# Power_Management_RFMC_RTM.net
KiCad netlist of a schematic drawn in Altium Designer
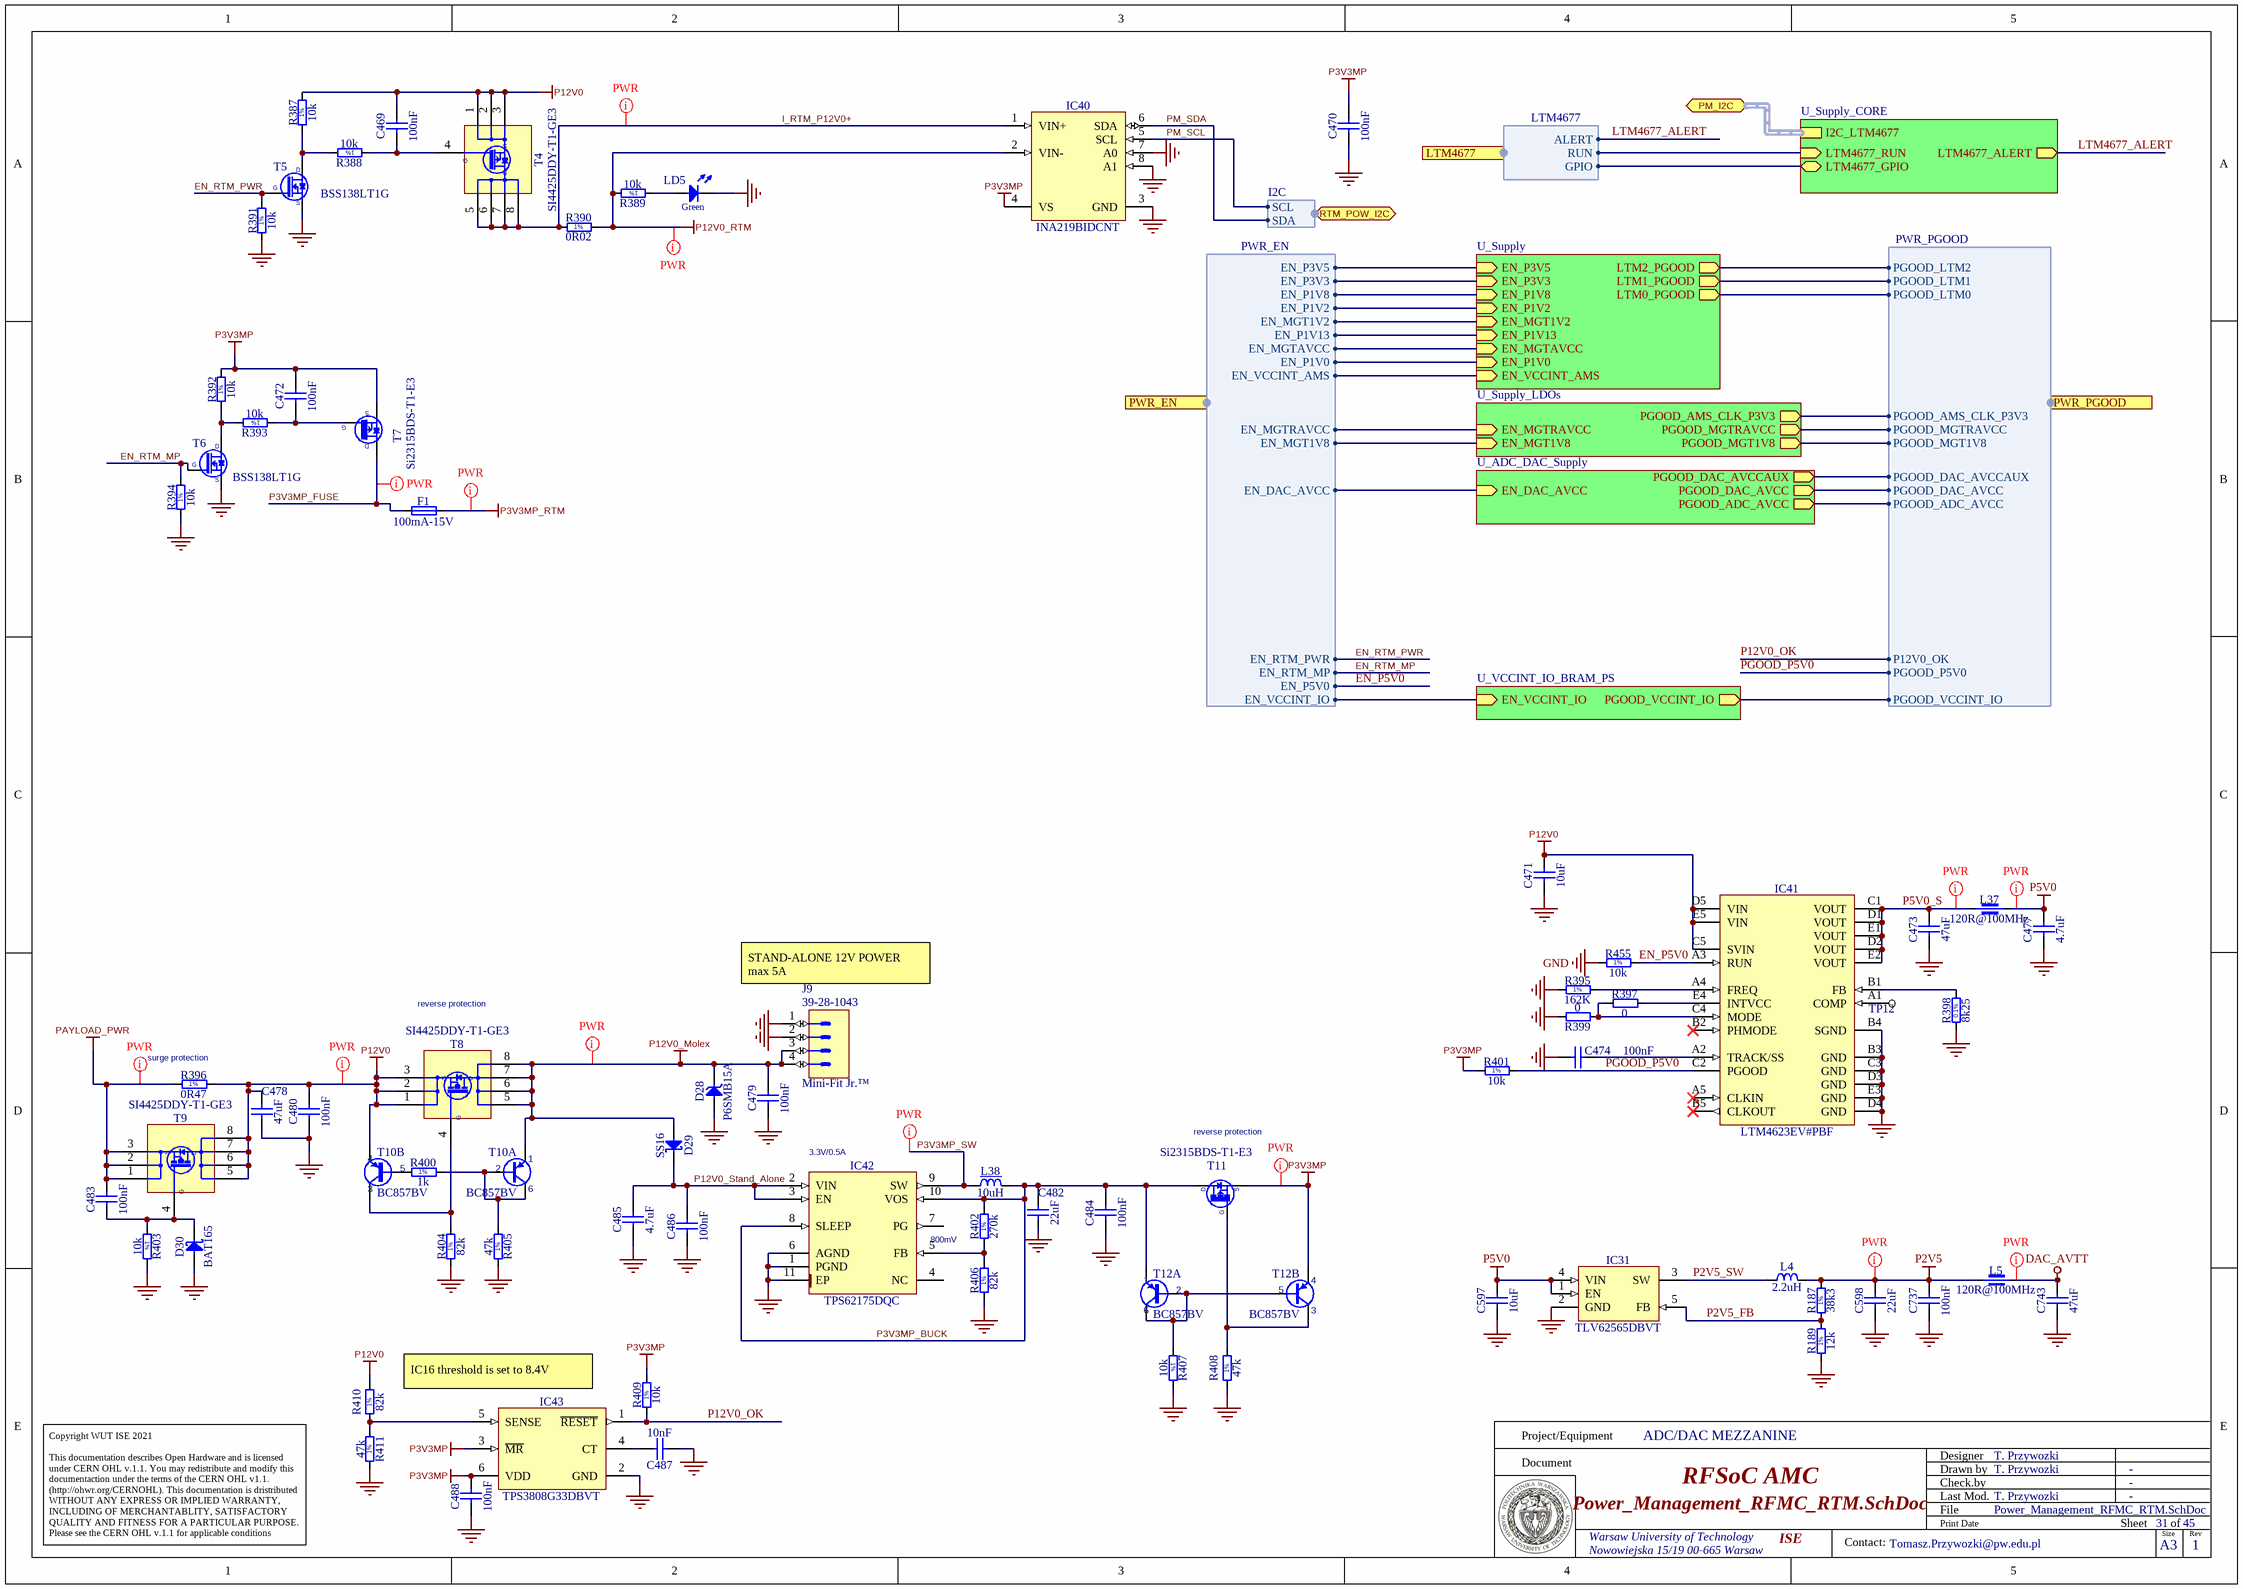
[diagram p0: Power_Management_RFMC_RTM.SchDoc]

(export (version "E")
  (design (tool "Eeschema 10.0.6"))
  (components
    (comp (ref "C469")
      (value "100nF")
      (footprint "CAPC1005X55N")
      (description "Non-polarised capacitor")
      (fields
        (field (name "MANUFACTURER PART NUMBER") "CC0402_100NF_16V_10%_X5R")
        (field (name "MANUFACTURER") "GENERIC")
        (field (name "AUTHOR") "CERN DEM JLC")
      )
      (libsource (lib "Capacitors") (part "Capacitor - non polarized"))
    )
    (comp (ref "C470")
      (value "100nF")
      (footprint "CAPC1005X55N")
      (description "Non-polarised capacitor")
      (fields
        (field (name "MANUFACTURER PART NUMBER") "CC0402_100NF_16V_10%_X5R")
        (field (name "MANUFACTURER") "GENERIC")
        (field (name "AUTHOR") "CERN DEM JLC")
      )
      (libsource (lib "Capacitors") (part "Capacitor - non polarized"))
    )
    (comp (ref "C471")
      (value "10uF")
      (footprint "CAPC2012X95N")
      (description "Non-polarised capacitor")
      (fields
        (field (name "PART NUMBER") "CC0805_10UF_25V_10%_X5R")
        (field (name "VOLTAGE") "25V")
        (field (name "AUTHOR") "CERN DEM JLC")
      )
      (libsource (lib "Capacitors") (part "Capacitor - non polarized"))
    )
    (comp (ref "C472")
      (value "100nF")
      (footprint "CAPC1005X55N")
      (description "Non-polarised capacitor")
      (fields
        (field (name "MANUFACTURER PART NUMBER") "CC0402_100NF_16V_10%_X5R")
        (field (name "MANUFACTURER") "GENERIC")
        (field (name "AUTHOR") "CERN DEM JLC")
      )
      (libsource (lib "Capacitors") (part "Capacitor - non polarized"))
    )
    (comp (ref "C473")
      (value "47uF")
      (footprint "CAPC2012X140N")
      (description "Non-polarised capacitor")
      (fields
        (field (name "MANUFACTURER PART NUMBER") "CC0805_47UF_6.3V_20%_X5R")
        (field (name "MANUFACTURER") "GENERIC")
        (field (name "AUTHOR") "CERN DEM JLC")
      )
      (libsource (lib "Capacitors") (part "Capacitor - non polarized"))
    )
    (comp (ref "C474")
      (value "100nF")
      (footprint "CAPC1005X55N")
      (description "Non-polarised capacitor")
      (fields
        (field (name "PART NUMBER") "CC0402_100NF_16V_10%_X5R")
        (field (name "VOLTAGE") "16V")
        (field (name "AUTHOR") "CERN DEM JLC")
      )
      (libsource (lib "Capacitors") (part "Capacitor - non polarized"))
    )
    (comp (ref "C477")
      (value "4.7uF")
      (footprint "CAPC1709X95N")
      (description "Non-polarised capacitor")
      (fields
        (field (name "MANUFACTURER PART NUMBER") "CC0603_4.7UF_16V_10%_X5R")
        (field (name "MANUFACTURER") "GENERIC")
        (field (name "AUTHOR") "CERN DEM JLC")
      )
      (libsource (lib "Capacitors") (part "Capacitor - non polarized"))
    )
    (comp (ref "C478")
      (value "47uF")
      (footprint "CAPC3216X180N")
      (description "Non-polarised capacitor")
      (fields
        (field (name "MANUFACTURER PART NUMBER") "CC1206_47UF_25V_20%_X5R")
        (field (name "MANUFACTURER") "GENERIC")
        (field (name "AUTHOR") "CERN DEM JLC")
      )
      (libsource (lib "Capacitors") (part "Capacitor - non polarized"))
    )
    (comp (ref "C479")
      (value "100nF")
      (footprint "CAPC1005X55N")
      (description "Non-polarised capacitor")
      (fields
        (field (name "MANUFACTURER PART NUMBER") "CC0402_100NF_16V_10%_X5R")
        (field (name "MANUFACTURER") "GENERIC")
        (field (name "AUTHOR") "CERN DEM JLC")
      )
      (libsource (lib "Capacitors") (part "Capacitor - non polarized"))
    )
    (comp (ref "C480")
      (value "100nF")
      (footprint "CAPC1005X55N")
      (description "Non-polarised capacitor")
      (fields
        (field (name "MANUFACTURER PART NUMBER") "CC0402_100NF_16V_10%_X5R")
        (field (name "MANUFACTURER") "GENERIC")
        (field (name "AUTHOR") "CERN DEM JLC")
      )
      (libsource (lib "Capacitors") (part "Capacitor - non polarized"))
    )
    (comp (ref "C482")
      (value "22uF")
      (footprint "CAPC2012X135N")
      (description "Non-polarised capacitor")
      (fields
        (field (name "MANUFACTURER PART NUMBER") "CC0805_22UF_16V_10%_X5R")
        (field (name "MANUFACTURER") "GENERIC")
        (field (name "AUTHOR") "CERN DEM JLC")
      )
      (libsource (lib "Capacitors") (part "Capacitor - non polarized"))
    )
    (comp (ref "C483")
      (value "100nF")
      (footprint "CAPC1005X55N")
      (description "Non-polarised capacitor")
      (fields
        (field (name "MANUFACTURER PART NUMBER") "CC0402_100NF_16V_10%_X5R")
        (field (name "MANUFACTURER") "GENERIC")
        (field (name "AUTHOR") "CERN DEM JLC")
      )
      (libsource (lib "Capacitors") (part "Capacitor - non polarized"))
    )
    (comp (ref "C484")
      (value "100nF")
      (footprint "CAPC1005X55N")
      (description "Non-polarised capacitor")
      (fields
        (field (name "MANUFACTURER PART NUMBER") "CC0402_100NF_16V_10%_X5R")
        (field (name "MANUFACTURER") "GENERIC")
        (field (name "AUTHOR") "CERN DEM JLC")
      )
      (libsource (lib "Capacitors") (part "Capacitor - non polarized"))
    )
    (comp (ref "C485")
      (value "4.7uF")
      (footprint "CAPC1709X95N")
      (description "Non-polarised capacitor")
      (fields
        (field (name "MANUFACTURER PART NUMBER") "CC0603_4.7UF_16V_10%_X5R")
        (field (name "MANUFACTURER") "GENERIC")
        (field (name "AUTHOR") "CERN DEM JLC")
      )
      (libsource (lib "Capacitors") (part "Capacitor - non polarized"))
    )
    (comp (ref "C486")
      (value "100nF")
      (footprint "CAPC1005X55N")
      (description "Non-polarised capacitor")
      (fields
        (field (name "MANUFACTURER PART NUMBER") "CC0402_100NF_16V_10%_X5R")
        (field (name "MANUFACTURER") "GENERIC")
        (field (name "AUTHOR") "CERN DEM JLC")
      )
      (libsource (lib "Capacitors") (part "Capacitor - non polarized"))
    )
    (comp (ref "C487")
      (value "10nF")
      (footprint "CAPC1005X55N")
      (description "Non-polarised capacitor")
      (fields
        (field (name "MANUFACTURER PART NUMBER") "CC0402_10NF_16V_10%_X7R")
        (field (name "MANUFACTURER") "GENERIC")
        (field (name "AUTHOR") "CERN DEM JLC")
      )
      (libsource (lib "Capacitors") (part "Capacitor - non polarized"))
    )
    (comp (ref "C488")
      (value "100nF")
      (footprint "CAPC1005X55N")
      (description "Non-polarised capacitor")
      (fields
        (field (name "MANUFACTURER PART NUMBER") "CC0402_100NF_16V_10%_X5R")
        (field (name "MANUFACTURER") "GENERIC")
        (field (name "AUTHOR") "CERN DEM JLC")
      )
      (libsource (lib "Capacitors") (part "Capacitor - non polarized"))
    )
    (comp (ref "C597")
      (value "10uF")
      (footprint "CAPC2012X95N")
      (description "Non-polarised capacitor")
      (fields
        (field (name "PART NUMBER") "CC0805_10UF_25V_10%_X5R")
        (field (name "VOLTAGE") "25V")
        (field (name "AUTHOR") "CERN DEM JLC")
      )
      (libsource (lib "Capacitors") (part "Capacitor - non polarized"))
    )
    (comp (ref "C598")
      (value "22uF")
      (footprint "CAPC1709X100N")
      (description "Non-polarised capacitor")
      (fields
        (field (name "PART NUMBER") "CC0603_22UF_6.3V_20%_X5R")
        (field (name "VOLTAGE") "6.3V")
        (field (name "AUTHOR") "CERN DEM JLC")
      )
      (libsource (lib "Capacitors") (part "Capacitor - non polarized"))
    )
    (comp (ref "C737")
      (value "100nF")
      (footprint "CAPC1005X55N")
      (description "Non-polarised capacitor")
      (fields
        (field (name "MANUFACTURER PART NUMBER") "CC0402_100NF_16V_10%_X5R")
        (field (name "MANUFACTURER") "GENERIC")
        (field (name "AUTHOR") "CERN DEM JLC")
      )
      (libsource (lib "Capacitors") (part "Capacitor - non polarized"))
    )
    (comp (ref "C743")
      (value "47uF")
      (footprint "CAPC2012X140N")
      (description "Non-polarised capacitor")
      (fields
        (field (name "MANUFACTURER PART NUMBER") "CC0805_47UF_6.3V_20%_X5R")
        (field (name "MANUFACTURER") "GENERIC")
        (field (name "AUTHOR") "CERN DEM JLC")
      )
      (libsource (lib "Capacitors") (part "Capacitor - non polarized"))
    )
    (comp (ref "D28")
      (value "P6SMB15A")
      (footprint "DIOM5436X261N")
      (description "Transient Voltage Suppressor Diode (Uni-Directional)")
      (fields
        (field (name "MANUFACTURER") "LITTELFUSE")
        (field (name "VOLTAGE") "15V")
        (field (name "AUTHOR") "CERN DEM JLC")
      )
      (libsource (lib "ICs And Semiconductors") (part "Diode TVS Uni-Directional"))
    )
    (comp (ref "D29")
      (value "SS16")
      (footprint "DIOM5127X229N")
      (description "Schottky Diode")
      (fields
        (field (name "MANUFACTURER") "VISHAY GENERAL SEMICONDUCTOR")
        (field (name "VOLTAGE") "60V")
        (field (name "AUTHOR") "CERN DEM JLC")
      )
      (libsource (lib "ICs And Semiconductors") (part "Diode Schottky"))
    )
    (comp (ref "D30")
      (value "BAT165")
      (footprint "SOD2512X110N")
      (description "Schottky Diode")
      (fields
        (field (name "MANUFACTURER") "INFINEON")
        (field (name "VOLTAGE") "40V")
        (field (name "AUTHOR") "CERN DEM JLC")
      )
      (libsource (lib "ICs And Semiconductors") (part "Diode Schottky"))
    )
    (comp (ref "F1")
      (value "100mA-15V")
      (footprint "FUSR_LITTELFUSE_0805L010")
      (description "Fuse")
      (fields
        (field (name "MANUFACTURER PART NUMBER") "0805L010YR")
        (field (name "MANUFACTURER") "LITTELFUSE")
        (field (name "AUTHOR") "CERN DEM JLC")
      )
      (libsource (lib "Eletro-mechanical") (part "Fuse"))
    )
    (comp (ref "IC31")
      (value "TLV62565DBVT")
      (footprint "SOT95P280X145-5N")
      (description "1.5A High Efficiency Step-Down Converter, Adjustable Output Voltage")
      (fields (field (name "MANUFACTURER") "TEXAS INSTRUMENTS") (field (name "AUTHOR") "CERN DEM JMW"))
      (libsource (lib "ICs And Semiconductors") (part "TLV62565"))
    )
    (comp (ref "IC40")
      (value "INA219BIDCNT")
      (footprint "SOT65P280X145-8N")
      (description "Zero-Drift, Bi-Directional CURRENT/POWER MONITOR with I2C™ Interface")
      (fields (field (name "MANUFACTURER") "TEXAS INSTRUMENTS") (field (name "AUTHOR") "CERN DEM JLC"))
      (libsource (lib "ICs And Semiconductors") (part "INA219BIDCNT"))
    )
    (comp (ref "IC41")
      (value "LTM4623EV#PBF")
      (footprint "LGA25C127P5X5_625X625X192")
      (description "4V-20V to 0.6V-5.5V, Iout 3A Step-Down DC/DC uModule Regulator")
      (fields (field (name "MANUFACTURER") "LINEAR TECHNOLOGY") (field (name "AUTHOR") "CERN DEM JMW"))
      (libsource (lib "ICs And Semiconductors") (part "LTM4623"))
    )
    (comp (ref "IC42")
      (value "TPS62175DQC")
      (footprint "SON50P200X300X80-11N-R94X250")
      (description "4.75-28VDC to 1-6VDC, 500mA Step-Down Converter With Sleep Mode")
      (fields (field (name "MANUFACTURER") "TEXAS INSTRUMENTS") (field (name "AUTHOR") "CERN DEM JMW"))
      (libsource (lib "ICs And Semiconductors") (part "TPS62175"))
    )
    (comp (ref "IC43")
      (value "TPS3808G33DBVT")
      (footprint "SOT95P280X145-6N")
      (description "Low Quiescent Current, Programmable-Delay Supervisory Circuit")
      (fields (field (name "MANUFACTURER") "TEXAS INSTRUMENTS") (field (name "AUTHOR") "CERN DEM JLC"))
      (libsource (lib "ICs And Semiconductors") (part "TPS3808xxxDBV"))
    )
    (comp (ref "J9")
      (value "Mini-Fit Jr.™")
      (footprint "MOLEX_39-28-1043")
      (description "Connector 4 Male")
      (fields
        (field (name "MANUFACTURER PART NUMBER") "39-28-1043")
        (field (name "MANUFACTURER") "MOLEX")
        (field (name "PART NUMBER") "MOLEX_39-28-1043")
        (field (name "AUTHOR") "CERN DEM JLC")
      )
      (libsource (lib "Connectors") (part "Connector 4 Male"))
    )
    (comp (ref "L4")
      (value "2.2uH")
      (footprint "IND_WURTH_WE-PMCI_0806LR")
      (description "Inductor")
      (fields
        (field (name "PART NUMBER") "IND_2.2UH_20%_WURTH_WE-PMCI_74479276222C")
        (field (name "POWER") "1.1A")
        (field (name "AUTHOR") "CERN DEM JLC")
      )
      (libsource (lib "Inductors & Transformers") (part "Inductor"))
    )
    (comp (ref "L5")
      (value "120R@100MHz")
      (footprint "INDC1608X95N")
      (fields
        (field (name "MANUFACTURER PART NUMBER") "BLM18PG121SN1D")
        (field (name "MANUFACTURER") "MURATA")
        (field (name "PART NUMBER") "IND0603_MURATA_BLM18PG121SN1D")
        (field (name "AUTHOR") "CERN DEM BC")
      )
      (libsource (lib "Inductors & Transformers") (part "Ferrite Bead"))
    )
    (comp (ref "L37")
      (value "120R@100MHz")
      (footprint "INDC1608X95N")
      (fields
        (field (name "MANUFACTURER PART NUMBER") "BLM18PG121SN1D")
        (field (name "MANUFACTURER") "MURATA")
        (field (name "PART NUMBER") "IND0603_MURATA_BLM18PG121SN1D")
        (field (name "AUTHOR") "CERN DEM BC")
      )
      (libsource (lib "Inductors & Transformers") (part "Ferrite Bead"))
    )
    (comp (ref "L38")
      (value "10uH")
      (footprint "IND_MURATA-PS_8400")
      (description "Inductor With Core")
      (fields
        (field (name "MANUFACTURER PART NUMBER") "84103C")
        (field (name "MANUFACTURER") "MURATA POWER SOLUTIONS")
        (field (name "AUTHOR") "CERN DEM JLC")
      )
      (libsource (lib "Inductors & Transformers") (part "Inductor With Magnetic core"))
    )
    (comp (ref "LD5")
      (value "Green")
      (footprint "LED_KINGBRIGHT_KPH-1608CGCK")
      (description "LED Green 1C 2A")
      (fields
        (field (name "MANUFACTURER PART NUMBER") "KPH-1608CGCK")
        (field (name "MANUFACTURER") "KINGBRIGHT")
        (field (name "AUTHOR") "CERN DEM JLC")
      )
      (libsource (lib "ICs And Semiconductors") (part "LED Green 1C 2A"))
    )
    (comp (ref "R187")
      (value "38k3")
      (footprint "RESC1005X40N")
      (description "Resistor - 1%")
      (fields
        (field (name "PART NUMBER") "R0402_38K3_1%_0.0625W_100PPM")
        (field (name "POWER") "0.0625W")
        (field (name "AUTHOR") "CERN DEM BC")
      )
      (libsource (lib "Resistors") (part "Resistor - 1%"))
    )
    (comp (ref "R189")
      (value "12k")
      (footprint "RESC1005X40N")
      (description "Resistor - 1%")
      (fields
        (field (name "PART NUMBER") "R0402_12K_1%_0.0625W_100PPM")
        (field (name "POWER") "0.0625W")
        (field (name "AUTHOR") "CERN DEM JLC")
      )
      (libsource (lib "Resistors") (part "Resistor - 1%"))
    )
    (comp (ref "R387")
      (value "10k")
      (footprint "RESC1005X40N")
      (description "Resistor - 1%")
      (fields
        (field (name "MANUFACTURER PART NUMBER") "R0402_10K_1%_0.0625W_100PPM")
        (field (name "MANUFACTURER") "GENERIC")
        (field (name "AUTHOR") "CERN DEM JLC")
      )
      (libsource (lib "Resistors") (part "Resistor - 1%"))
    )
    (comp (ref "R388")
      (value "10k")
      (footprint "RESC1005X40N")
      (description "Resistor - 1%")
      (fields
        (field (name "MANUFACTURER PART NUMBER") "R0402_10K_1%_0.0625W_100PPM")
        (field (name "MANUFACTURER") "GENERIC")
        (field (name "AUTHOR") "CERN DEM JLC")
      )
      (libsource (lib "Resistors") (part "Resistor - 1%"))
    )
    (comp (ref "R389")
      (value "10k")
      (footprint "RESC1005X40N")
      (description "Resistor - 1%")
      (fields
        (field (name "MANUFACTURER PART NUMBER") "R0402_10K_1%_0.0625W_100PPM")
        (field (name "MANUFACTURER") "GENERIC")
        (field (name "AUTHOR") "CERN DEM JLC")
      )
      (libsource (lib "Resistors") (part "Resistor - 1%"))
    )
    (comp (ref "R390")
      (value "0R02")
      (footprint "RESC_VISHAY_WSL2512_0R007-0R5")
      (description "Resistor - 1%")
      (fields
        (field (name "MANUFACTURER PART NUMBER") "WSL2512R0200FEA")
        (field (name "MANUFACTURER") "VISHAY DALE")
        (field (name "AUTHOR") "CERN DEM JLC")
      )
      (libsource (lib "Resistors") (part "Resistor - 1%"))
    )
    (comp (ref "R391")
      (value "10k")
      (footprint "RESC1005X40N")
      (description "Resistor - 1%")
      (fields
        (field (name "MANUFACTURER PART NUMBER") "R0402_10K_1%_0.0625W_100PPM")
        (field (name "MANUFACTURER") "GENERIC")
        (field (name "AUTHOR") "CERN DEM JLC")
      )
      (libsource (lib "Resistors") (part "Resistor - 1%"))
    )
    (comp (ref "R392")
      (value "10k")
      (footprint "RESC1005X40N")
      (description "Resistor - 1%")
      (fields
        (field (name "MANUFACTURER PART NUMBER") "R0402_10K_1%_0.0625W_100PPM")
        (field (name "MANUFACTURER") "GENERIC")
        (field (name "AUTHOR") "CERN DEM JLC")
      )
      (libsource (lib "Resistors") (part "Resistor - 1%"))
    )
    (comp (ref "R393")
      (value "10k")
      (footprint "RESC1005X40N")
      (description "Resistor - 1%")
      (fields
        (field (name "MANUFACTURER PART NUMBER") "R0402_10K_1%_0.0625W_100PPM")
        (field (name "MANUFACTURER") "GENERIC")
        (field (name "AUTHOR") "CERN DEM JLC")
      )
      (libsource (lib "Resistors") (part "Resistor - 1%"))
    )
    (comp (ref "R394")
      (value "10k")
      (footprint "RESC1005X40N")
      (description "Resistor - 1%")
      (fields
        (field (name "MANUFACTURER PART NUMBER") "R0402_10K_1%_0.0625W_100PPM")
        (field (name "MANUFACTURER") "GENERIC")
        (field (name "AUTHOR") "CERN DEM JLC")
      )
      (libsource (lib "Resistors") (part "Resistor - 1%"))
    )
    (comp (ref "R395")
      (value "162K")
      (footprint "RESC1608X55N")
      (description "Resistor - 1%")
      (fields
        (field (name "PART NUMBER") "R0603_162K_1%_0.1W_100PPM")
        (field (name "POWER") "0.1W")
        (field (name "AUTHOR") "CERN DEM BC")
      )
      (libsource (lib "Resistors") (part "Resistor - 1%"))
    )
    (comp (ref "R396")
      (value "0R47")
      (footprint "RESC3216X65N")
      (description "Resistor - 1%")
      (fields
        (field (name "MANUFACTURER PART NUMBER") "RL1206FR-7W0R47  (35051914707)")
        (field (name "MANUFACTURER") "YAGEO PHYCOMP")
        (field (name "AUTHOR") "CERN DEM JLC")
      )
      (libsource (lib "Resistors") (part "Resistor - 1%"))
    )
    (comp (ref "R397")
      (value "0")
      (footprint "RESC1005X40N")
      (description "Resistor")
      (fields
        (field (name "MANUFACTURER PART NUMBER") "R0402_0R_JUMPER")
        (field (name "MANUFACTURER") "GENERIC")
        (field (name "AUTHOR") "CERN DEM JLC")
      )
      (libsource (lib "Resistors") (part "Resistor"))
    )
    (comp (ref "R398")
      (value "8k25")
      (footprint "RESC1608X55N")
      (description "Resistor - 0.1%")
      (fields
        (field (name "PART NUMBER") "R0603_8K25_0.1%_0.063W_10PPM")
        (field (name "POWER") "0.063W")
        (field (name "AUTHOR") "CERN DEM JLC")
      )
      (libsource (lib "Resistors") (part "Resistor - 0.1%"))
    )
    (comp (ref "R399")
      (value "0")
      (footprint "RESC1005X40N")
      (description "Resistor")
      (fields
        (field (name "MANUFACTURER PART NUMBER") "R0402_0R_JUMPER")
        (field (name "MANUFACTURER") "GENERIC")
        (field (name "AUTHOR") "CERN DEM JLC")
      )
      (libsource (lib "Resistors") (part "Resistor"))
    )
    (comp (ref "R400")
      (value "1k")
      (footprint "RESC1005X40N")
      (description "Resistor - 1%")
      (fields
        (field (name "MANUFACTURER PART NUMBER") "R0402_1K_1%_0.0625W_100PPM")
        (field (name "MANUFACTURER") "GENERIC")
        (field (name "AUTHOR") "CERN DEM JLC")
      )
      (libsource (lib "Resistors") (part "Resistor - 1%"))
    )
    (comp (ref "R401")
      (value "10k")
      (footprint "RESC1005X40N")
      (description "Resistor - 1%")
      (fields
        (field (name "MANUFACTURER PART NUMBER") "R0402_10K_1%_0.0625W_100PPM")
        (field (name "MANUFACTURER") "GENERIC")
        (field (name "AUTHOR") "CERN DEM JLC")
      )
      (libsource (lib "Resistors") (part "Resistor - 1%"))
    )
    (comp (ref "R402")
      (value "270k")
      (footprint "RESC1005X40N")
      (description "Resistor - 1%")
      (fields
        (field (name "MANUFACTURER PART NUMBER") "R0402_270K_1%_0.0625W_100PPM")
        (field (name "MANUFACTURER") "GENERIC")
        (field (name "AUTHOR") "CERN DEM JLC")
      )
      (libsource (lib "Resistors") (part "Resistor - 1%"))
    )
    (comp (ref "R403")
      (value "10k")
      (footprint "RESC1005X40N")
      (description "Resistor - 1%")
      (fields
        (field (name "MANUFACTURER PART NUMBER") "R0402_10K_1%_0.0625W_100PPM")
        (field (name "MANUFACTURER") "GENERIC")
        (field (name "AUTHOR") "CERN DEM JLC")
      )
      (libsource (lib "Resistors") (part "Resistor - 1%"))
    )
    (comp (ref "R404")
      (value "82k")
      (footprint "RESC1005X40N")
      (description "Resistor - 1%")
      (fields
        (field (name "MANUFACTURER PART NUMBER") "R0402_82K_1%_0.0625W_100PPM")
        (field (name "MANUFACTURER") "GENERIC")
        (field (name "AUTHOR") "CERN DEM JLC")
      )
      (libsource (lib "Resistors") (part "Resistor - 1%"))
    )
    (comp (ref "R405")
      (value "47k")
      (footprint "RESC1005X40N")
      (description "Resistor - 1%")
      (fields
        (field (name "MANUFACTURER PART NUMBER") "R0402_47K_1%_0.0625W_100PPM")
        (field (name "MANUFACTURER") "GENERIC")
        (field (name "AUTHOR") "CERN DEM JLC")
      )
      (libsource (lib "Resistors") (part "Resistor - 1%"))
    )
    (comp (ref "R406")
      (value "82k")
      (footprint "RESC1005X40N")
      (description "Resistor - 1%")
      (fields
        (field (name "MANUFACTURER PART NUMBER") "R0402_82K_1%_0.0625W_100PPM")
        (field (name "MANUFACTURER") "GENERIC")
        (field (name "AUTHOR") "CERN DEM JLC")
      )
      (libsource (lib "Resistors") (part "Resistor - 1%"))
    )
    (comp (ref "R407")
      (value "10k")
      (footprint "RESC1005X40N")
      (description "Resistor - 1%")
      (fields
        (field (name "MANUFACTURER PART NUMBER") "R0402_10K_1%_0.0625W_100PPM")
        (field (name "MANUFACTURER") "GENERIC")
        (field (name "AUTHOR") "CERN DEM JLC")
      )
      (libsource (lib "Resistors") (part "Resistor - 1%"))
    )
    (comp (ref "R408")
      (value "47k")
      (footprint "RESC1005X40N")
      (description "Resistor - 1%")
      (fields
        (field (name "MANUFACTURER PART NUMBER") "R0402_47K_1%_0.0625W_100PPM")
        (field (name "MANUFACTURER") "GENERIC")
        (field (name "AUTHOR") "CERN DEM JLC")
      )
      (libsource (lib "Resistors") (part "Resistor - 1%"))
    )
    (comp (ref "R409")
      (value "10k")
      (footprint "RESC1005X40N")
      (description "Resistor - 1%")
      (fields
        (field (name "MANUFACTURER PART NUMBER") "R0402_10K_1%_0.0625W_100PPM")
        (field (name "MANUFACTURER") "GENERIC")
        (field (name "AUTHOR") "CERN DEM JLC")
      )
      (libsource (lib "Resistors") (part "Resistor - 1%"))
    )
    (comp (ref "R410")
      (value "82k")
      (footprint "RESC1005X40N")
      (description "Resistor - 1%")
      (fields
        (field (name "MANUFACTURER PART NUMBER") "R0402_82K_1%_0.0625W_100PPM")
        (field (name "MANUFACTURER") "GENERIC")
        (field (name "AUTHOR") "CERN DEM JLC")
      )
      (libsource (lib "Resistors") (part "Resistor - 1%"))
    )
    (comp (ref "R411")
      (value "47k")
      (footprint "RESC1005X40N")
      (description "Resistor - 1%")
      (fields
        (field (name "MANUFACTURER PART NUMBER") "R0402_47K_1%_0.0625W_100PPM")
        (field (name "MANUFACTURER") "GENERIC")
        (field (name "AUTHOR") "CERN DEM JLC")
      )
      (libsource (lib "Resistors") (part "Resistor - 1%"))
    )
    (comp (ref "R455")
      (value "10k")
      (footprint "RESC1005X40N")
      (description "Resistor - 1%")
      (fields
        (field (name "MANUFACTURER PART NUMBER") "R0402_10K_1%_0.0625W_100PPM")
        (field (name "MANUFACTURER") "GENERIC")
        (field (name "AUTHOR") "CERN DEM JLC")
      )
      (libsource (lib "Resistors") (part "Resistor - 1%"))
    )
    (comp (ref "T4")
      (value "SI4425DDY-T1-GE3")
      (footprint "SOIC127P600X175-8N")
      (description "-30V -19.7A P-Channel MOSFET")
      (fields (field (name "MANUFACTURER") "VISHAY SILICONIX") (field (name "AUTHOR") "CERN DEM MR"))
      (libsource (lib "") (part "SI4425DDY_1"))
    )
    (comp (ref "T5")
      (value "BSS138LT1G")
      (footprint "SOT95P240X110-3N")
      (description "N-CHANNEL MOSFET WITH DIODE")
      (fields (field (name "MANUFACTURER") "ON SEMICONDUCTOR") (field (name "AUTHOR") "CERN DEM JLC"))
      (libsource (lib "ICs And Semiconductors") (part "N-MOSFET-D 1G 2S 3D"))
    )
    (comp (ref "T6")
      (value "BSS138LT1G")
      (footprint "SOT95P240X110-3N")
      (description "N-CHANNEL MOSFET WITH DIODE")
      (fields (field (name "MANUFACTURER") "ON SEMICONDUCTOR") (field (name "AUTHOR") "CERN DEM JLC"))
      (libsource (lib "ICs And Semiconductors") (part "N-MOSFET-D 1G 2S 3D"))
    )
    (comp (ref "T7")
      (value "Si2315BDS-T1-E3")
      (footprint "SOT95P237X112-3N")
      (description "P-CHANNEL MOSFET WITH DIODE")
      (fields (field (name "MANUFACTURER") "VISHAY SILICONIX") (field (name "AUTHOR") "CERN DEM JLC"))
      (libsource (lib "ICs And Semiconductors") (part "P-MOSFET-D 1G 2S 3D"))
    )
    (comp (ref "T8")
      (value "SI4425DDY-T1-GE3")
      (footprint "SOIC127P600X175-8N")
      (description "-30V -19.7A P-Channel MOSFET")
      (fields (field (name "MANUFACTURER") "VISHAY SILICONIX") (field (name "AUTHOR") "CERN DEM MR"))
      (libsource (lib "ICs And Semiconductors") (part "SI4425DDY"))
    )
    (comp (ref "T9")
      (value "SI4425DDY-T1-GE3")
      (footprint "SOIC127P600X175-8N")
      (description "-30V -19.7A P-Channel MOSFET")
      (fields (field (name "MANUFACTURER") "VISHAY SILICONIX") (field (name "AUTHOR") "CERN DEM MR"))
      (libsource (lib "ICs And Semiconductors") (part "SI4425DDY"))
    )
    (comp (ref "T10")
      (value "BC857BV")
      (footprint "SOTFL50P160X60-6N")
      (description "45V, 100mA PNP General Purpose Double Transistor")
      (fields (field (name "MANUFACTURER") "NXP SEMICONDUCTORS") (field (name "AUTHOR") "CERN DEM JLC"))
      (libsource (lib "") (part "BC857BV_1"))
    )
    (comp (ref "T11")
      (value "Si2315BDS-T1-E3")
      (footprint "SOT95P237X112-3N")
      (description "P-CHANNEL MOSFET WITH DIODE")
      (fields (field (name "MANUFACTURER") "VISHAY SILICONIX") (field (name "AUTHOR") "CERN DEM JLC"))
      (libsource (lib "ICs And Semiconductors") (part "P-MOSFET-D 1G 2S 3D"))
    )
    (comp (ref "T12")
      (value "BC857BV")
      (footprint "SOTFL50P160X60-6N")
      (description "45V, 100mA PNP General Purpose Double Transistor")
      (fields (field (name "MANUFACTURER") "NXP SEMICONDUCTORS") (field (name "AUTHOR") "CERN DEM JLC"))
      (libsource (lib "") (part "BC857BV_1"))
    )
    (comp (ref "TP12")
      (value "TP")
      (footprint "TP")
      (description "Testpoint")
      (libsource (lib "LIBRARY_SCH") (part "TP"))
    )
  )
  (nets
    (net (code "17") (name "/EN_P5V0") (class "Default")
      (node (ref "IC41") (pin "A3") (pinfunction "RUN_A3") (pintype "input"))
      (node (ref "R455") (pin "2") (pinfunction "2_2") (pintype "passive"))
    )
    (net (code "18") (name "/EN_RTM_MP") (class "Default")
      (node (ref "R394") (pin "2") (pinfunction "2_2") (pintype "passive"))
      (node (ref "T6") (pin "1") (pinfunction "G_1") (pintype "passive"))
    )
    (net (code "19") (name "/EN_RTM_PWR") (class "Default")
      (node (ref "R391") (pin "2") (pinfunction "2_2") (pintype "passive"))
      (node (ref "T5") (pin "1") (pinfunction "G_1") (pintype "passive"))
    )
    (net (code "22") (name "/I_RTM_P12V0+") (class "Default")
      (node (ref "IC40") (pin "1") (pinfunction "VIN+_1") (pintype "input"))
      (node (ref "R390") (pin "1") (pinfunction "1_1") (pintype "passive"))
      (node (ref "T4") (pin "5") (pinfunction "D_5") (pintype "passive"))
      (node (ref "T4") (pin "6") (pinfunction "D_6") (pintype "passive"))
      (node (ref "T4") (pin "7") (pinfunction "D_7") (pintype "passive"))
      (node (ref "T4") (pin "8") (pinfunction "D_8") (pintype "passive"))
    )
    (net (code "29") (name "/P2V5_FB") (class "Default")
      (node (ref "IC31") (pin "5") (pinfunction "FB_5") (pintype "input"))
      (node (ref "R187") (pin "1") (pinfunction "1_1") (pintype "passive"))
      (node (ref "R189") (pin "2") (pinfunction "2_2") (pintype "passive"))
    )
    (net (code "30") (name "/P2V5_SW") (class "Default")
      (node (ref "IC31") (pin "3") (pinfunction "SW_3") (pintype "power_in"))
      (node (ref "L4") (pin "1") (pinfunction "1_1") (pintype "passive"))
    )
    (net (code "31") (name "/P3V3MP_BUCK") (class "Default")
      (node (ref "C482") (pin "2") (pinfunction "2_2") (pintype "passive"))
      (node (ref "C484") (pin "2") (pinfunction "2_2") (pintype "passive"))
      (node (ref "IC42") (pin "10") (pinfunction "VOS_10") (pintype "input"))
      (node (ref "IC42") (pin "8") (pinfunction "SLEEP_8") (pintype "input"))
      (node (ref "L38") (pin "2") (pinfunction "2_2") (pintype "passive"))
      (node (ref "R402") (pin "2") (pinfunction "2_2") (pintype "passive"))
      (node (ref "T11") (pin "3") (pinfunction "D_3") (pintype "passive"))
      (node (ref "T12") (pin "1") (pinfunction "E_1") (pintype "passive"))
    )
    (net (code "32") (name "/P3V3MP_FUSE") (class "Default")
      (node (ref "F1") (pin "1") (pinfunction "1_1") (pintype "passive"))
      (node (ref "T7") (pin "3") (pinfunction "D_3") (pintype "passive"))
    )
    (net (code "33") (name "/P3V3MP_SW") (class "Default")
      (node (ref "IC42") (pin "9") (pinfunction "SW_9") (pintype "output"))
      (node (ref "L38") (pin "1") (pinfunction "1_1") (pintype "passive"))
    )
    (net (code "34") (name "/P5V0_S") (class "Default")
      (node (ref "C473") (pin "2") (pinfunction "2_2") (pintype "passive"))
      (node (ref "IC41") (pin "C1") (pinfunction "VOUT_C1") (pintype "power_in"))
      (node (ref "IC41") (pin "D1") (pinfunction "VOUT_D1") (pintype "power_in"))
      (node (ref "IC41") (pin "D2") (pinfunction "VOUT_D2") (pintype "power_in"))
      (node (ref "IC41") (pin "E1") (pinfunction "VOUT_E1") (pintype "power_in"))
      (node (ref "IC41") (pin "E2") (pinfunction "VOUT_E2") (pintype "power_in"))
      (node (ref "L37") (pin "1") (pinfunction "1_1") (pintype "passive"))
    )
    (net (code "35") (name "/P12V0_OK") (class "Default")
      (node (ref "IC43") (pin "1") (pinfunction "~{RESET}_1") (pintype "output"))
      (node (ref "R409") (pin "1") (pinfunction "1_1") (pintype "passive"))
    )
    (net (code "36") (name "/P12V0_Stand_Alone") (class "Default")
      (node (ref "C485") (pin "2") (pinfunction "2_2") (pintype "passive"))
      (node (ref "C486") (pin "2") (pinfunction "2_2") (pintype "passive"))
      (node (ref "D29") (pin "1") (pinfunction "C_1") (pintype "passive"))
      (node (ref "IC42") (pin "2") (pinfunction "VIN_2") (pintype "input"))
      (node (ref "IC42") (pin "3") (pinfunction "EN_3") (pintype "input"))
    )
    (net (code "43") (name "/PGOOD_P5V0") (class "Default")
      (node (ref "IC41") (pin "C2") (pinfunction "PGOOD_C2") (pintype "open_collector"))
      (node (ref "R401") (pin "2") (pinfunction "2_2") (pintype "passive"))
    )
    (net (code "46") (name "/PM_SCL") (class "Default")
      (node (ref "IC40") (pin "5") (pinfunction "SCL_5") (pintype "input"))
    )
    (net (code "47") (name "/PM_SDA") (class "Default")
      (node (ref "IC40") (pin "6") (pinfunction "SDA_6") (pintype "bidirectional"))
    )
    (net (code "52") (name "DAC_AVTT") (class "Default")
      (node (ref "C743") (pin "2") (pinfunction "2_2") (pintype "passive"))
      (node (ref "L5") (pin "2") (pinfunction "2_2") (pintype "passive"))
    )
    (net (code "53") (name "GND") (class "Default")
      (node (ref "C470") (pin "1") (pinfunction "1_1") (pintype "passive"))
      (node (ref "C471") (pin "1") (pinfunction "1_1") (pintype "passive"))
      (node (ref "C473") (pin "1") (pinfunction "1_1") (pintype "passive"))
      (node (ref "C474") (pin "2") (pinfunction "2_2") (pintype "passive"))
      (node (ref "C477") (pin "1") (pinfunction "1_1") (pintype "passive"))
      (node (ref "C478") (pin "1") (pinfunction "1_1") (pintype "passive"))
      (node (ref "C479") (pin "1") (pinfunction "1_1") (pintype "passive"))
      (node (ref "C480") (pin "1") (pinfunction "1_1") (pintype "passive"))
      (node (ref "C482") (pin "1") (pinfunction "1_1") (pintype "passive"))
      (node (ref "C484") (pin "1") (pinfunction "1_1") (pintype "passive"))
      (node (ref "C485") (pin "1") (pinfunction "1_1") (pintype "passive"))
      (node (ref "C486") (pin "1") (pinfunction "1_1") (pintype "passive"))
      (node (ref "C487") (pin "1") (pinfunction "1_1") (pintype "passive"))
      (node (ref "C488") (pin "1") (pinfunction "1_1") (pintype "passive"))
      (node (ref "C597") (pin "1") (pinfunction "1_1") (pintype "passive"))
      (node (ref "C598") (pin "1") (pinfunction "1_1") (pintype "passive"))
      (node (ref "C737") (pin "1") (pinfunction "1_1") (pintype "passive"))
      (node (ref "C743") (pin "1") (pinfunction "1_1") (pintype "passive"))
      (node (ref "D28") (pin "2") (pinfunction "A_2") (pintype "passive"))
      (node (ref "D30") (pin "2") (pinfunction "A_2") (pintype "passive"))
      (node (ref "IC31") (pin "2") (pinfunction "GND_2") (pintype "power_in"))
      (node (ref "IC40") (pin "3") (pinfunction "GND_3") (pintype "power_in"))
      (node (ref "IC40") (pin "7") (pinfunction "A0_7") (pintype "input"))
      (node (ref "IC40") (pin "8") (pinfunction "A1_8") (pintype "input"))
      (node (ref "IC41") (pin "B3") (pinfunction "GND_B3") (pintype "power_in"))
      (node (ref "IC41") (pin "B4") (pinfunction "SGND_B4") (pintype "power_in"))
      (node (ref "IC41") (pin "C3") (pinfunction "GND_C3") (pintype "power_in"))
      (node (ref "IC41") (pin "D3") (pinfunction "GND_D3") (pintype "power_in"))
      (node (ref "IC41") (pin "D4") (pinfunction "GND_D4") (pintype "power_in"))
      (node (ref "IC41") (pin "E3") (pinfunction "GND_E3") (pintype "power_in"))
      (node (ref "IC42") (pin "1") (pinfunction "PGND_1") (pintype "power_in"))
      (node (ref "IC42") (pin "11") (pinfunction "EP_11") (pintype "power_in"))
      (node (ref "IC42") (pin "6") (pinfunction "AGND_6") (pintype "power_in"))
      (node (ref "IC43") (pin "2") (pinfunction "GND_2") (pintype "power_in"))
      (node (ref "J9") (pin "1") (pinfunction "1_1") (pintype "bidirectional"))
      (node (ref "J9") (pin "2") (pinfunction "2_2") (pintype "bidirectional"))
      (node (ref "LD5") (pin "1") (pinfunction "C_1") (pintype "passive"))
      (node (ref "R189") (pin "1") (pinfunction "1_1") (pintype "passive"))
      (node (ref "R391") (pin "1") (pinfunction "1_1") (pintype "passive"))
      (node (ref "R394") (pin "1") (pinfunction "1_1") (pintype "passive"))
      (node (ref "R395") (pin "1") (pinfunction "1_1") (pintype "passive"))
      (node (ref "R398") (pin "1") (pinfunction "1_1") (pintype "passive"))
      (node (ref "R399") (pin "2") (pinfunction "2_2") (pintype "passive"))
      (node (ref "R403") (pin "2") (pinfunction "2_2") (pintype "passive"))
      (node (ref "R404") (pin "1") (pinfunction "1_1") (pintype "passive"))
      (node (ref "R405") (pin "1") (pinfunction "1_1") (pintype "passive"))
      (node (ref "R406") (pin "1") (pinfunction "1_1") (pintype "passive"))
      (node (ref "R407") (pin "2") (pinfunction "2_2") (pintype "passive"))
      (node (ref "R408") (pin "1") (pinfunction "1_1") (pintype "passive"))
      (node (ref "R411") (pin "1") (pinfunction "1_1") (pintype "passive"))
      (node (ref "R455") (pin "1") (pinfunction "1_1") (pintype "passive"))
      (node (ref "T5") (pin "2") (pinfunction "S_2") (pintype "passive"))
      (node (ref "T6") (pin "2") (pinfunction "S_2") (pintype "passive"))
    )
    (net (code "54") (name "Net-(C469-Pad1)") (class "Default")
      (node (ref "C469") (pin "1") (pinfunction "1_1") (pintype "passive"))
      (node (ref "R388") (pin "1") (pinfunction "1_1") (pintype "passive"))
      (node (ref "T4") (pin "4") (pinfunction "S_4") (pintype "passive"))
    )
    (net (code "55") (name "Net-(D30-C)") (class "Default")
      (node (ref "C483") (pin "1") (pinfunction "1_1") (pintype "passive"))
      (node (ref "D30") (pin "1") (pinfunction "C_1") (pintype "passive"))
      (node (ref "R403") (pin "1") (pinfunction "1_1") (pintype "passive"))
      (node (ref "T9") (pin "4") (pinfunction "S_4") (pintype "passive"))
    )
    (net (code "56") (name "Net-(IC41-COMP)") (class "Default")
      (node (ref "IC41") (pin "A1") (pinfunction "COMP_A1") (pintype "input"))
      (node (ref "TP12") (pin "1") (pintype "passive"))
    )
    (net (code "57") (name "Net-(IC41-FB)") (class "Default")
      (node (ref "IC41") (pin "B1") (pinfunction "FB_B1") (pintype "input"))
      (node (ref "R398") (pin "2") (pinfunction "2_2") (pintype "passive"))
    )
    (net (code "58") (name "Net-(IC41-FREQ)") (class "Default")
      (node (ref "IC41") (pin "A4") (pinfunction "FREQ_A4") (pintype "input"))
      (node (ref "R395") (pin "2") (pinfunction "2_2") (pintype "passive"))
    )
    (net (code "59") (name "Net-(IC41-INTVCC)") (class "Default")
      (node (ref "IC41") (pin "E4") (pinfunction "INTVCC_E4") (pintype "power_in"))
      (node (ref "R397") (pin "2") (pinfunction "2_2") (pintype "passive"))
    )
    (net (code "60") (name "Net-(IC41-MODE)") (class "Default")
      (node (ref "IC41") (pin "C4") (pinfunction "MODE_C4") (pintype "input"))
      (node (ref "R397") (pin "1") (pinfunction "1_1") (pintype "passive"))
      (node (ref "R399") (pin "1") (pinfunction "1_1") (pintype "passive"))
    )
    (net (code "61") (name "Net-(IC41-TRACK{slash}SS)") (class "Default")
      (node (ref "C474") (pin "1") (pinfunction "1_1") (pintype "passive"))
      (node (ref "IC41") (pin "A2") (pinfunction "TRACK/SS_A2") (pintype "input"))
    )
    (net (code "62") (name "Net-(IC42-FB)") (class "Default")
      (node (ref "IC42") (pin "5") (pinfunction "FB_5") (pintype "input"))
      (node (ref "R402") (pin "1") (pinfunction "1_1") (pintype "passive"))
      (node (ref "R406") (pin "2") (pinfunction "2_2") (pintype "passive"))
    )
    (net (code "63") (name "Net-(IC43-CT)") (class "Default")
      (node (ref "C487") (pin "2") (pinfunction "2_2") (pintype "passive"))
      (node (ref "IC43") (pin "4") (pinfunction "CT_4") (pintype "passive"))
    )
    (net (code "64") (name "Net-(IC43-SENSE)") (class "Default")
      (node (ref "IC43") (pin "5") (pinfunction "SENSE_5") (pintype "input"))
      (node (ref "R410") (pin "1") (pinfunction "1_1") (pintype "passive"))
      (node (ref "R411") (pin "2") (pinfunction "2_2") (pintype "passive"))
    )
    (net (code "65") (name "Net-(LD5-A)") (class "Default")
      (node (ref "LD5") (pin "2") (pinfunction "A_2") (pintype "passive"))
      (node (ref "R389") (pin "1") (pinfunction "1_1") (pintype "passive"))
    )
    (net (code "66") (name "Net-(T5-D)") (class "Default")
      (node (ref "R387") (pin "1") (pinfunction "1_1") (pintype "passive"))
      (node (ref "R388") (pin "2") (pinfunction "2_2") (pintype "passive"))
      (node (ref "T5") (pin "3") (pinfunction "D_3") (pintype "passive"))
    )
    (net (code "67") (name "Net-(T6-D)") (class "Default")
      (node (ref "R392") (pin "1") (pinfunction "1_1") (pintype "passive"))
      (node (ref "R393") (pin "2") (pinfunction "2_2") (pintype "passive"))
      (node (ref "T6") (pin "3") (pinfunction "D_3") (pintype "passive"))
    )
    (net (code "68") (name "Net-(T7-G)") (class "Default")
      (node (ref "C472") (pin "1") (pinfunction "1_1") (pintype "passive"))
      (node (ref "R393") (pin "1") (pinfunction "1_1") (pintype "passive"))
      (node (ref "T7") (pin "1") (pinfunction "G_1") (pintype "passive"))
    )
    (net (code "69") (name "Net-(T10A-B)") (class "Default")
      (node (ref "R400") (pin "2") (pinfunction "2_2") (pintype "passive"))
      (node (ref "R405") (pin "2") (pinfunction "2_2") (pintype "passive"))
      (node (ref "T10") (pin "2") (pinfunction "B_2") (pintype "passive"))
      (node (ref "T10") (pin "6") (pinfunction "C_6") (pintype "passive"))
    )
    (net (code "70") (name "Net-(T10B-B)") (class "Default")
      (node (ref "R400") (pin "1") (pinfunction "1_1") (pintype "passive"))
      (node (ref "T10") (pin "5") (pinfunction "B_5") (pintype "passive"))
    )
    (net (code "71") (name "Net-(T10B-C)") (class "Default")
      (node (ref "R404") (pin "2") (pinfunction "2_2") (pintype "passive"))
      (node (ref "T10") (pin "3") (pinfunction "C_3") (pintype "passive"))
      (node (ref "T8") (pin "4") (pinfunction "S_4") (pintype "passive"))
    )
    (net (code "72") (name "Net-(T11-G)") (class "Default")
      (node (ref "R408") (pin "2") (pinfunction "2_2") (pintype "passive"))
      (node (ref "T11") (pin "1") (pinfunction "G_1") (pintype "passive"))
      (node (ref "T12") (pin "3") (pinfunction "C_3") (pintype "passive"))
    )
    (net (code "73") (name "Net-(T12A-B)") (class "Default")
      (node (ref "R407") (pin "1") (pinfunction "1_1") (pintype "passive"))
      (node (ref "T12") (pin "2") (pinfunction "B_2") (pintype "passive"))
      (node (ref "T12") (pin "5") (pinfunction "B_5") (pintype "passive"))
      (node (ref "T12") (pin "6") (pinfunction "C_6") (pintype "passive"))
    )
    (net (code "74") (name "P2V5") (class "Default")
      (node (ref "C598") (pin "2") (pinfunction "2_2") (pintype "passive"))
      (node (ref "C737") (pin "2") (pinfunction "2_2") (pintype "passive"))
      (node (ref "L4") (pin "2") (pinfunction "2_2") (pintype "passive"))
      (node (ref "L5") (pin "1") (pinfunction "1_1") (pintype "passive"))
      (node (ref "R187") (pin "2") (pinfunction "2_2") (pintype "passive"))
    )
    (net (code "75") (name "P3V3MP") (class "Default")
      (node (ref "C470") (pin "2") (pinfunction "2_2") (pintype "passive"))
      (node (ref "C472") (pin "2") (pinfunction "2_2") (pintype "passive"))
      (node (ref "C488") (pin "2") (pinfunction "2_2") (pintype "passive"))
      (node (ref "IC40") (pin "4") (pinfunction "VS_4") (pintype "power_in"))
      (node (ref "IC43") (pin "3") (pinfunction "~{MR}_3") (pintype "input"))
      (node (ref "IC43") (pin "6") (pinfunction "VDD_6") (pintype "power_in"))
      (node (ref "R392") (pin "2") (pinfunction "2_2") (pintype "passive"))
      (node (ref "R401") (pin "1") (pinfunction "1_1") (pintype "passive"))
      (node (ref "R409") (pin "2") (pinfunction "2_2") (pintype "passive"))
      (node (ref "T11") (pin "2") (pinfunction "S_2") (pintype "passive"))
      (node (ref "T12") (pin "4") (pinfunction "E_4") (pintype "passive"))
      (node (ref "T7") (pin "2") (pinfunction "S_2") (pintype "passive"))
    )
    (net (code "76") (name "P3V3MP_RTM") (class "Default")
      (node (ref "F1") (pin "2") (pinfunction "2_2") (pintype "passive"))
    )
    (net (code "77") (name "P5V0") (class "Default")
      (node (ref "C477") (pin "2") (pinfunction "2_2") (pintype "passive"))
      (node (ref "C597") (pin "2") (pinfunction "2_2") (pintype "passive"))
      (node (ref "IC31") (pin "1") (pinfunction "EN_1") (pintype "input"))
      (node (ref "IC31") (pin "4") (pinfunction "VIN_4") (pintype "input"))
      (node (ref "L37") (pin "2") (pinfunction "2_2") (pintype "passive"))
    )
    (net (code "78") (name "P12V0") (class "Default")
      (node (ref "C469") (pin "2") (pinfunction "2_2") (pintype "passive"))
      (node (ref "C471") (pin "2") (pinfunction "2_2") (pintype "passive"))
      (node (ref "C478") (pin "2") (pinfunction "2_2") (pintype "passive"))
      (node (ref "C480") (pin "2") (pinfunction "2_2") (pintype "passive"))
      (node (ref "IC41") (pin "C5") (pinfunction "SVIN_C5") (pintype "power_in"))
      (node (ref "IC41") (pin "D5") (pinfunction "VIN_D5") (pintype "power_in"))
      (node (ref "IC41") (pin "E5") (pinfunction "VIN_E5") (pintype "power_in"))
      (node (ref "R387") (pin "2") (pinfunction "2_2") (pintype "passive"))
      (node (ref "R396") (pin "2") (pinfunction "2_2") (pintype "passive"))
      (node (ref "R410") (pin "2") (pinfunction "2_2") (pintype "passive"))
      (node (ref "T10") (pin "4") (pinfunction "E_4") (pintype "passive"))
      (node (ref "T4") (pin "1") (pinfunction "S_1") (pintype "passive"))
      (node (ref "T4") (pin "2") (pinfunction "S_2") (pintype "passive"))
      (node (ref "T4") (pin "3") (pinfunction "S_3") (pintype "passive"))
      (node (ref "T8") (pin "1") (pinfunction "S_1") (pintype "passive"))
      (node (ref "T8") (pin "2") (pinfunction "S_2") (pintype "passive"))
      (node (ref "T8") (pin "3") (pinfunction "S_3") (pintype "passive"))
      (node (ref "T9") (pin "5") (pinfunction "D_5") (pintype "passive"))
      (node (ref "T9") (pin "6") (pinfunction "D_6") (pintype "passive"))
      (node (ref "T9") (pin "7") (pinfunction "D_7") (pintype "passive"))
      (node (ref "T9") (pin "8") (pinfunction "D_8") (pintype "passive"))
    )
    (net (code "79") (name "P12V0_Molex") (class "Default")
      (node (ref "C479") (pin "2") (pinfunction "2_2") (pintype "passive"))
      (node (ref "D28") (pin "1") (pinfunction "C_1") (pintype "passive"))
      (node (ref "D29") (pin "2") (pinfunction "A_2") (pintype "passive"))
      (node (ref "J9") (pin "3") (pinfunction "3_3") (pintype "bidirectional"))
      (node (ref "J9") (pin "4") (pinfunction "4_4") (pintype "bidirectional"))
      (node (ref "T10") (pin "1") (pinfunction "E_1") (pintype "passive"))
      (node (ref "T8") (pin "5") (pinfunction "D_5") (pintype "passive"))
      (node (ref "T8") (pin "6") (pinfunction "D_6") (pintype "passive"))
      (node (ref "T8") (pin "7") (pinfunction "D_7") (pintype "passive"))
      (node (ref "T8") (pin "8") (pinfunction "D_8") (pintype "passive"))
    )
    (net (code "80") (name "P12V0_RTM") (class "Default")
      (node (ref "IC40") (pin "2") (pinfunction "VIN-_2") (pintype "input"))
      (node (ref "R389") (pin "2") (pinfunction "2_2") (pintype "passive"))
      (node (ref "R390") (pin "2") (pinfunction "2_2") (pintype "passive"))
    )
    (net (code "81") (name "PAYLOAD_PWR") (class "Default")
      (node (ref "C483") (pin "2") (pinfunction "2_2") (pintype "passive"))
      (node (ref "R396") (pin "1") (pinfunction "1_1") (pintype "passive"))
      (node (ref "T9") (pin "1") (pinfunction "S_1") (pintype "passive"))
      (node (ref "T9") (pin "2") (pinfunction "S_2") (pintype "passive"))
      (node (ref "T9") (pin "3") (pinfunction "S_3") (pintype "passive"))
    )
    (net (code "82") (name "unconnected-(IC41-CLKIN-PadA5)") (class "Default")
      (node (ref "IC41") (pin "A5") (pinfunction "CLKIN_A5") (pintype "input+no_connect"))
    )
    (net (code "83") (name "unconnected-(IC41-CLKOUT-PadB5)") (class "Default")
      (node (ref "IC41") (pin "B5") (pinfunction "CLKOUT_B5") (pintype "output+no_connect"))
    )
    (net (code "84") (name "unconnected-(IC41-PHMODE-PadB2)") (class "Default")
      (node (ref "IC41") (pin "B2") (pinfunction "PHMODE_B2") (pintype "input+no_connect"))
    )
    (net (code "85") (name "unconnected-(IC42-NC-Pad4)") (class "Default")
      (node (ref "IC42") (pin "4") (pinfunction "NC_4") (pintype "passive"))
    )
    (net (code "86") (name "unconnected-(IC42-PG-Pad7)") (class "Default")
      (node (ref "IC42") (pin "7") (pinfunction "PG_7") (pintype "output"))
    )
  )
)
